# YOTSUBA_-Y-Z_ver_1_2b.net
KiCad netlist of a schematic drawn in EAGLE
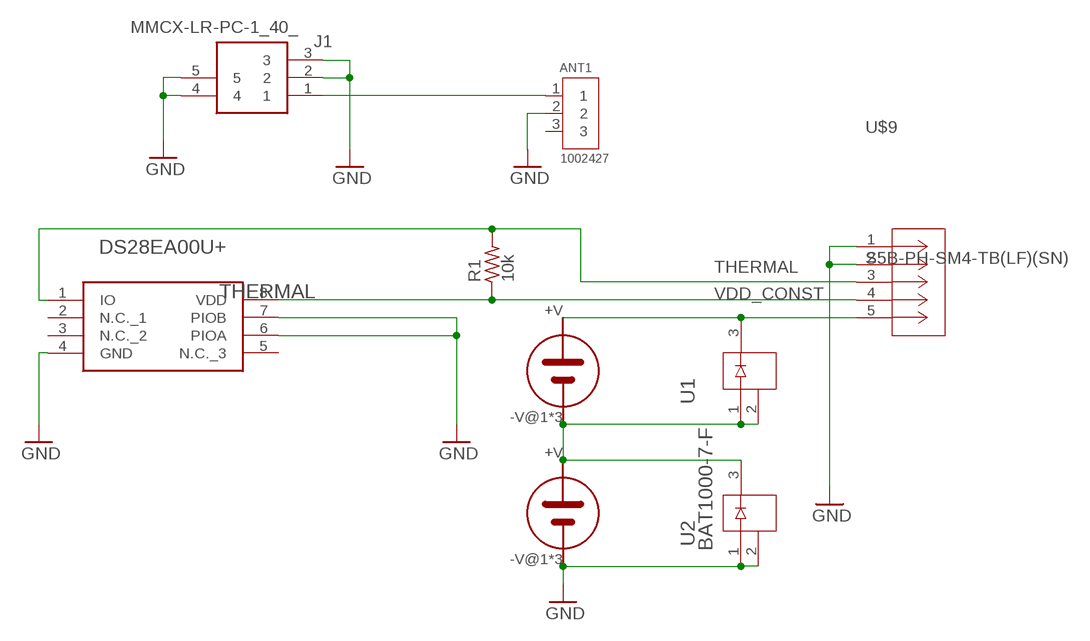
[diagram p0: schematic, sheet 1]

(export (version "E")
  (design (tool "Eeschema 10.0.6"))
  (components
    (comp (ref "ANT1")
      (value "1002427")
      (footprint "eagle-import:ANTENNA_1002427")
      (fields (field (name "DIGI-KEY_PART_NUMBER") "478-1002427TR-ND") (field (name "MF") "Ethertronics/AVX"))
      (libsource (lib "eagle-import") (part "1002427"))
    )
    (comp (ref "J1")
      (value "MMCX-LR-PC-1_40_")
      (footprint "eagle-import:MMCXLRPC140")
      (fields
        (field (name "MANUFACTURER_PART_NUMBER") "MMCX-LR-PC-1(40)")
        (field (name "MOUSER_PART_NUMBER") "798-MMCX-LR-PC-1(40)")
      )
      (libsource (lib "eagle-import") (part "MMCX-LR-PC-1_40_"))
    )
    (comp (ref "R1")
      (value "10k")
      (footprint "eagle-import:R0805")
      (libsource (lib "eagle-import") (part "R-US_R0805"))
    )
    (comp (ref "THERMAL")
      (value "DS28EA00U+")
      (footprint "eagle-import:SOP65P490X110-8N")
      (fields (field (name "MOUSER_PART_NUMBER") "700-DS28EA00U"))
      (libsource (lib "eagle-import") (part "DS28EA00U+"))
    )
    (comp (ref "U$2")
      (value "3G30A")
      (footprint "eagle-import:SOLAR_3G30A")
      (libsource (lib "eagle-import") (part "3G30A"))
    )
    (comp (ref "U$3")
      (value "3G30A")
      (footprint "eagle-import:SOLAR_3G30A")
      (libsource (lib "eagle-import") (part "3G30A"))
    )
    (comp (ref "U$9")
      (value "S5B-PH-SM4-TB(LF)(SN)")
      (footprint "eagle-import:CONN_S5B-PH-SM4-TB_JST")
      (fields (field (name "COPYRIGHT") "Copyright (C) 2023 Ultra Librarian. All rights reserved."))
      (libsource (lib "eagle-import") (part "S5B-PH-SM4-TB(LF)(SN)"))
    )
    (comp (ref "U1")
      (value "BAT1000-7-F")
      (footprint "eagle-import:SOT23_BAT_DIO")
      (fields (field (name "COPYRIGHT") "Copyright (C) 2023 Ultra Librarian. All rights reserved."))
      (libsource (lib "eagle-import") (part "BAT1000-7-F"))
    )
    (comp (ref "U2")
      (value "BAT1000-7-F")
      (footprint "eagle-import:SOT23_BAT_DIO")
      (fields (field (name "COPYRIGHT") "Copyright (C) 2023 Ultra Librarian. All rights reserved."))
      (libsource (lib "eagle-import") (part "BAT1000-7-F"))
    )
  )
  (nets
    (net (code "1") (name "/THERMAL") (class "Default")
      (node (ref "R1") (pin "2") (pinfunction "2_2") (pintype "passive"))
      (node (ref "THERMAL") (pin "1") (pinfunction "IO_1") (pintype "bidirectional"))
      (node (ref "U$9") (pin "3") (pinfunction "3_3") (pintype "passive"))
    )
    (net (code "2") (name "/VDD_CONST") (class "Default")
      (node (ref "R1") (pin "1") (pinfunction "1_1") (pintype "passive"))
      (node (ref "THERMAL") (pin "8") (pinfunction "VDD_8") (pintype "bidirectional"))
      (node (ref "U$9") (pin "4") (pinfunction "4_4") (pintype "passive"))
    )
    (net (code "3") (name "GND") (class "Default")
      (node (ref "ANT1") (pin "2") (pinfunction "2_2") (pintype "passive"))
      (node (ref "J1") (pin "2") (pinfunction "2_2") (pintype "bidirectional"))
      (node (ref "J1") (pin "3") (pinfunction "3_3") (pintype "bidirectional"))
      (node (ref "J1") (pin "4") (pinfunction "4_4") (pintype "bidirectional"))
      (node (ref "J1") (pin "5") (pinfunction "5_5") (pintype "bidirectional"))
      (node (ref "THERMAL") (pin "4") (pinfunction "GND_4") (pintype "bidirectional"))
      (node (ref "THERMAL") (pin "6") (pinfunction "PIOA_6") (pintype "bidirectional"))
      (node (ref "THERMAL") (pin "7") (pinfunction "PIOB_7") (pintype "bidirectional"))
      (node (ref "U$3") (pin "-V@1") (pinfunction "-V_-V@1") (pintype "bidirectional"))
      (node (ref "U$3") (pin "-V@2") (pinfunction "-V_-V@2") (pintype "bidirectional"))
      (node (ref "U$3") (pin "-V@3") (pinfunction "-V_-V@3") (pintype "bidirectional"))
      (node (ref "U$9") (pin "1") (pinfunction "1_1") (pintype "passive"))
      (node (ref "U$9") (pin "2") (pinfunction "2_2") (pintype "passive"))
      (node (ref "U2") (pin "1") (pinfunction "1_1") (pintype "passive"))
      (node (ref "U2") (pin "2") (pinfunction "2_2") (pintype "passive"))
    )
    (net (code "4") (name "Net-(ANT1-Pad1)") (class "Default")
      (node (ref "ANT1") (pin "1") (pinfunction "1_1") (pintype "passive"))
      (node (ref "J1") (pin "1") (pinfunction "1_1") (pintype "bidirectional"))
    )
    (net (code "5") (name "Net-(U$2--V-Pad-V@1)") (class "Default")
      (node (ref "U$2") (pin "-V@1") (pinfunction "-V_-V@1") (pintype "bidirectional"))
      (node (ref "U$2") (pin "-V@2") (pinfunction "-V_-V@2") (pintype "bidirectional"))
      (node (ref "U$2") (pin "-V@3") (pinfunction "-V_-V@3") (pintype "bidirectional"))
      (node (ref "U$3") (pin "+V") (pinfunction "+V_+V") (pintype "bidirectional"))
      (node (ref "U1") (pin "1") (pinfunction "1_1") (pintype "passive"))
      (node (ref "U1") (pin "2") (pinfunction "2_2") (pintype "passive"))
      (node (ref "U2") (pin "3") (pinfunction "3_3") (pintype "passive"))
    )
    (net (code "6") (name "Net-(U$2-Pad+V)") (class "Default")
      (node (ref "U$2") (pin "+V") (pinfunction "+V_+V") (pintype "bidirectional"))
      (node (ref "U$9") (pin "5") (pinfunction "5_5") (pintype "passive"))
      (node (ref "U1") (pin "3") (pinfunction "3_3") (pintype "passive"))
    )
    (net (code "7") (name "unconnected-(ANT1-Pad3)") (class "Default")
      (node (ref "ANT1") (pin "3") (pinfunction "3_3") (pintype "passive"))
    )
    (net (code "8") (name "unconnected-(THERMAL-N.C._1-Pad2)") (class "Default")
      (node (ref "THERMAL") (pin "2") (pinfunction "N.C._1_2") (pintype "bidirectional"))
    )
    (net (code "9") (name "unconnected-(THERMAL-N.C._2-Pad3)") (class "Default")
      (node (ref "THERMAL") (pin "3") (pinfunction "N.C._2_3") (pintype "bidirectional"))
    )
    (net (code "10") (name "unconnected-(THERMAL-N.C._3-Pad5)") (class "Default")
      (node (ref "THERMAL") (pin "5") (pinfunction "N.C._3_5") (pintype "bidirectional"))
    )
  )
)
